# Bridge.net
KiCad netlist of a schematic drawn in Altium Designer
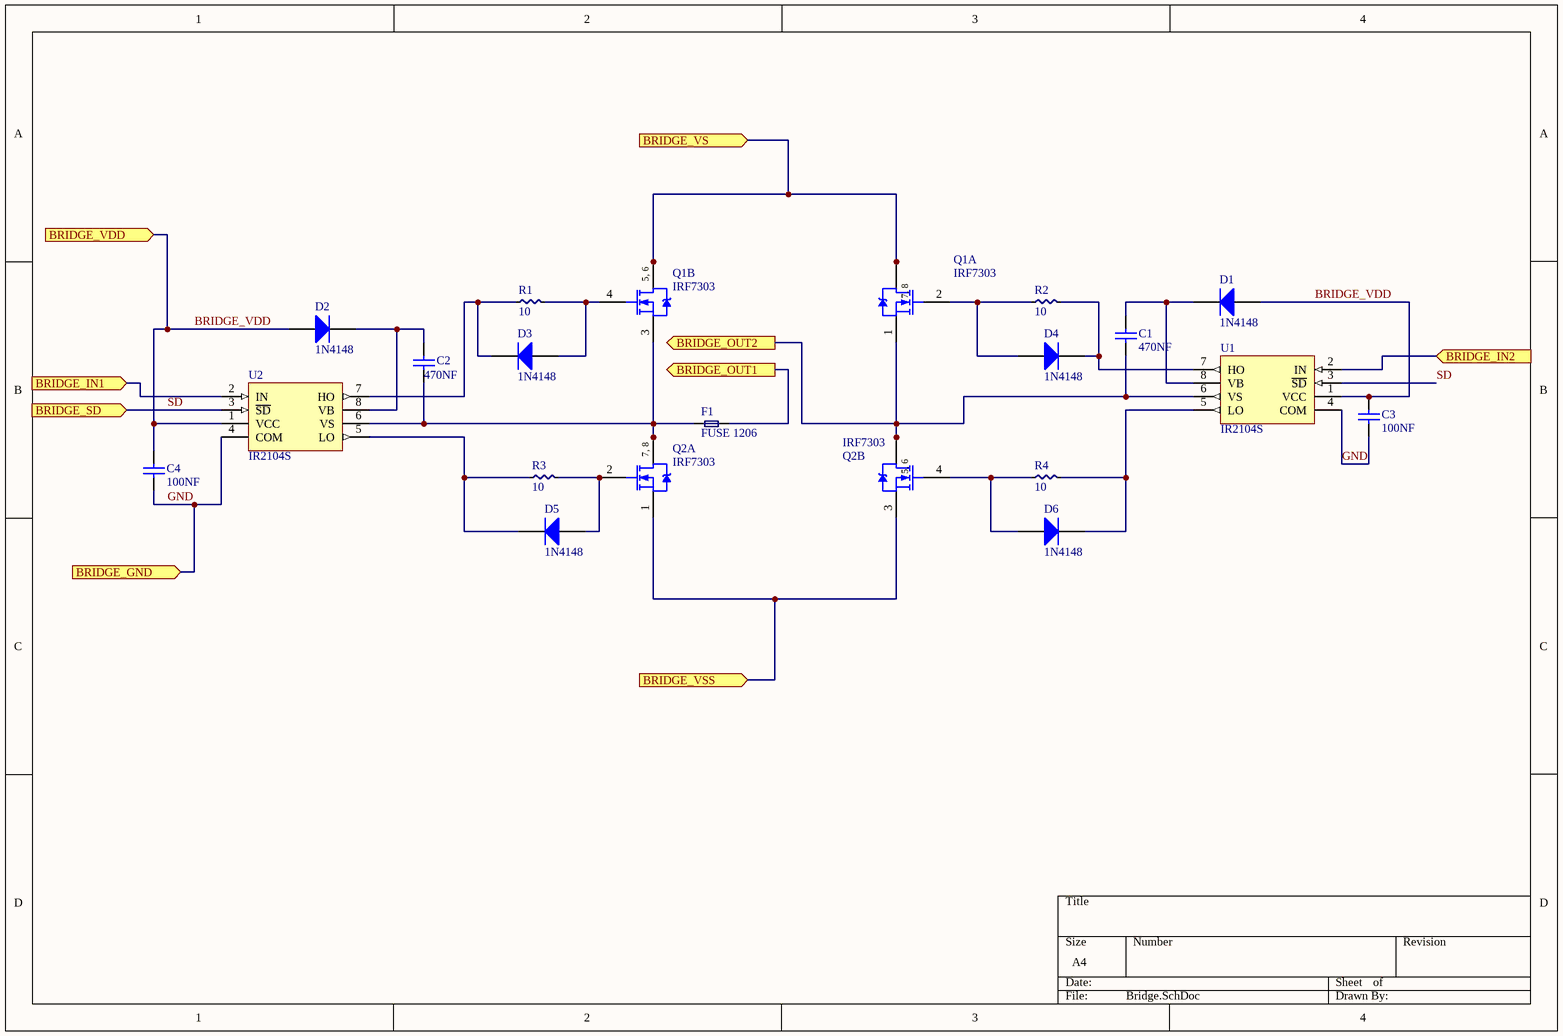
[diagram p0: Bridge.SchDoc]

(export (version "E")
  (design (tool "Eeschema 10.0.6"))
  (components
    (comp (ref "C1")
      (value "470NF")
      (footprint "MY_CAP_SMD_1206")
      (description "3.2 mm × 1.6 mm")
      (libsource (lib "AMINLIB") (part "CAP SMD_1206"))
    )
    (comp (ref "C2")
      (value "470NF")
      (footprint "MY_CAP_SMD_1206")
      (description "3.2 mm × 1.6 mm")
      (libsource (lib "AMINLIB") (part "CAP SMD_1206"))
    )
    (comp (ref "C3")
      (value "100NF")
      (footprint "MY_CAP_SMD_0805")
      (description "2.0 mm × 1.25 mm")
      (libsource (lib "AMINLIB") (part "CAP SMD_0805"))
    )
    (comp (ref "C4")
      (value "100NF")
      (footprint "MY_CAP_SMD_0805")
      (description "2.0 mm × 1.25 mm")
      (libsource (lib "AMINLIB") (part "CAP SMD_0805"))
    )
    (comp (ref "D1")
      (value "1N4148")
      (footprint "MY_DIOD1N5822_SMD")
      (libsource (lib "AMINLIB") (part "1N5822-smd-5*2mm"))
    )
    (comp (ref "D2")
      (value "1N4148")
      (footprint "MY_DIOD1N5822_SMD")
      (libsource (lib "AMINLIB") (part "1N5822-smd-5*2mm"))
    )
    (comp (ref "D3")
      (value "1N4148")
      (footprint "MY_DIOD1N5822_SMD")
      (libsource (lib "AMINLIB") (part "1N5822-smd-5*2mm"))
    )
    (comp (ref "D4")
      (value "1N4148")
      (footprint "MY_DIOD1N5822_SMD")
      (libsource (lib "AMINLIB") (part "1N5822-smd-5*2mm"))
    )
    (comp (ref "D5")
      (value "1N4148")
      (footprint "MY_DIOD1N5822_SMD")
      (libsource (lib "AMINLIB") (part "1N5822-smd-5*2mm"))
    )
    (comp (ref "D6")
      (value "1N4148")
      (footprint "MY_DIOD1N5822_SMD")
      (libsource (lib "AMINLIB") (part "1N5822-smd-5*2mm"))
    )
    (comp (ref "F1")
      (value "FUSE 1206")
      (footprint "FUSE1206")
      (libsource (lib "AMINLIB") (part "FUSE 1206"))
    )
    (comp (ref "Q1")
      (value "IRF7303")
      (footprint "SO-8_N")
      (description "HEXFET Power MOSFET")
      (fields (field (name "PUBLISHER") "Altium Limited"))
      (libsource (lib "IR Discrete MOSFET - Power") (part "IRF7303"))
    )
    (comp (ref "Q2")
      (value "IRF7303")
      (footprint "SO-8_N")
      (description "HEXFET Power MOSFET")
      (fields (field (name "PUBLISHER") "Altium Limited"))
      (libsource (lib "IR Discrete MOSFET - Power") (part "IRF7303"))
    )
    (comp (ref "R1")
      (value "10")
      (footprint "MY_RES_SMD_0805")
      (libsource (lib "AMINLIB") (part "RES SMD 0805"))
    )
    (comp (ref "R2")
      (value "10")
      (footprint "MY_RES_SMD_0805")
      (libsource (lib "AMINLIB") (part "RES SMD 0805"))
    )
    (comp (ref "R3")
      (value "10")
      (footprint "MY_RES_SMD_0805")
      (libsource (lib "AMINLIB") (part "RES SMD 0805"))
    )
    (comp (ref "R4")
      (value "10")
      (footprint "MY_RES_SMD_0805")
      (libsource (lib "AMINLIB") (part "RES SMD 0805"))
    )
    (comp (ref "U1")
      (value "IR2104S")
      (footprint "SO-8_N")
      (description "High and Low Side Driver")
      (fields (field (name "PUBLISHER") "Altium Limited"))
      (libsource (lib "") (part "IR2104S_1"))
    )
    (comp (ref "U2")
      (value "IR2104S")
      (footprint "SO-8_N")
      (description "High and Low Side Driver")
      (fields (field (name "PUBLISHER") "Altium Limited"))
      (libsource (lib "IR Interface Bridge Driver") (part "IR2104S"))
    )
  )
  (nets
    (net (code "1") (name "/BRIDGE_IN1") (class "Default")
      (node (ref "U2") (pin "2") (pinfunction "IN_2") (pintype "input"))
    )
    (net (code "2") (name "/BRIDGE_IN2") (class "Default")
      (node (ref "U1") (pin "2") (pinfunction "IN_2") (pintype "input"))
    )
    (net (code "3") (name "/BRIDGE_OUT1") (class "Default")
      (node (ref "F1") (pin "1") (pinfunction "1_1") (pintype "passive"))
    )
    (net (code "4") (name "/BRIDGE_OUT2") (class "Default")
      (node (ref "C1") (pin "1") (pinfunction "1_1") (pintype "passive"))
      (node (ref "Q1") (pin "1") (pinfunction "S_1") (pintype "passive"))
      (node (ref "Q2") (pin "5") (pinfunction "D_5") (pintype "passive"))
      (node (ref "Q2") (pin "6") (pinfunction "D_6") (pintype "passive"))
      (node (ref "U1") (pin "6") (pinfunction "VS_6") (pintype "output"))
    )
    (net (code "5") (name "/BRIDGE_VDD") (class "Default")
      (node (ref "C3") (pin "2") (pinfunction "2_2") (pintype "passive"))
      (node (ref "C4") (pin "2") (pinfunction "2_2") (pintype "passive"))
      (node (ref "D1") (pin "A") (pinfunction "A_A") (pintype "passive"))
      (node (ref "D2") (pin "A") (pinfunction "A_A") (pintype "passive"))
      (node (ref "U1") (pin "1") (pinfunction "VCC_1") (pintype "passive"))
      (node (ref "U2") (pin "1") (pinfunction "VCC_1") (pintype "passive"))
    )
    (net (code "6") (name "/BRIDGE_VS") (class "Default")
      (node (ref "Q1") (pin "5") (pinfunction "D_5") (pintype "passive"))
      (node (ref "Q1") (pin "6") (pinfunction "D_6") (pintype "passive"))
      (node (ref "Q1") (pin "7") (pinfunction "D_7") (pintype "passive"))
      (node (ref "Q1") (pin "8") (pinfunction "D_8") (pintype "passive"))
    )
    (net (code "7") (name "/BRIDGE_VSS") (class "Default")
      (node (ref "Q2") (pin "1") (pinfunction "S_1") (pintype "passive"))
      (node (ref "Q2") (pin "3") (pinfunction "S_3") (pintype "passive"))
    )
    (net (code "8") (name "/GND") (class "Default")
      (node (ref "C3") (pin "1") (pinfunction "1_1") (pintype "passive"))
      (node (ref "C4") (pin "1") (pinfunction "1_1") (pintype "passive"))
      (node (ref "U1") (pin "4") (pinfunction "COM_4") (pintype "passive"))
      (node (ref "U2") (pin "4") (pinfunction "COM_4") (pintype "passive"))
    )
    (net (code "9") (name "/SD") (class "Default")
      (node (ref "U1") (pin "3") (pinfunction "~{SD}_3") (pintype "input"))
      (node (ref "U2") (pin "3") (pinfunction "~{SD}_3") (pintype "input"))
    )
    (net (code "10") (name "Net-(Q1A-G)") (class "Default")
      (node (ref "D4") (pin "A") (pinfunction "A_A") (pintype "passive"))
      (node (ref "Q1") (pin "2") (pinfunction "G_2") (pintype "passive"))
      (node (ref "R2") (pin "1") (pinfunction "1_1") (pintype "passive"))
    )
    (net (code "11") (name "Net-(Q1B-G)") (class "Default")
      (node (ref "D3") (pin "A") (pinfunction "A_A") (pintype "passive"))
      (node (ref "Q1") (pin "4") (pinfunction "G_4") (pintype "passive"))
      (node (ref "R1") (pin "2") (pinfunction "2_2") (pintype "passive"))
    )
    (net (code "12") (name "Net-(Q1B-S)") (class "Default")
      (node (ref "C2") (pin "1") (pinfunction "1_1") (pintype "passive"))
      (node (ref "F1") (pin "2") (pinfunction "2_2") (pintype "passive"))
      (node (ref "Q1") (pin "3") (pinfunction "S_3") (pintype "passive"))
      (node (ref "Q2") (pin "7") (pinfunction "D_7") (pintype "passive"))
      (node (ref "Q2") (pin "8") (pinfunction "D_8") (pintype "passive"))
      (node (ref "U2") (pin "6") (pinfunction "VS_6") (pintype "power_in"))
    )
    (net (code "13") (name "Net-(Q2A-G)") (class "Default")
      (node (ref "D5") (pin "A") (pinfunction "A_A") (pintype "passive"))
      (node (ref "Q2") (pin "2") (pinfunction "G_2") (pintype "passive"))
      (node (ref "R3") (pin "2") (pinfunction "2_2") (pintype "passive"))
    )
    (net (code "14") (name "Net-(Q2B-G)") (class "Default")
      (node (ref "D6") (pin "A") (pinfunction "A_A") (pintype "passive"))
      (node (ref "Q2") (pin "4") (pinfunction "G_4") (pintype "passive"))
      (node (ref "R4") (pin "1") (pinfunction "1_1") (pintype "passive"))
    )
    (net (code "15") (name "Net-(U1-HO)") (class "Default")
      (node (ref "D4") (pin "K") (pinfunction "K_K") (pintype "passive"))
      (node (ref "R2") (pin "2") (pinfunction "2_2") (pintype "passive"))
      (node (ref "U1") (pin "7") (pinfunction "HO_7") (pintype "output"))
    )
    (net (code "16") (name "Net-(U1-LO)") (class "Default")
      (node (ref "D6") (pin "K") (pinfunction "K_K") (pintype "passive"))
      (node (ref "R4") (pin "2") (pinfunction "2_2") (pintype "passive"))
      (node (ref "U1") (pin "5") (pinfunction "LO_5") (pintype "output"))
    )
    (net (code "17") (name "Net-(U1-VB)") (class "Default")
      (node (ref "C1") (pin "2") (pinfunction "2_2") (pintype "passive"))
      (node (ref "D1") (pin "K") (pinfunction "K_K") (pintype "passive"))
      (node (ref "U1") (pin "8") (pinfunction "VB_8") (pintype "power_in"))
    )
    (net (code "18") (name "Net-(U2-HO)") (class "Default")
      (node (ref "D3") (pin "K") (pinfunction "K_K") (pintype "passive"))
      (node (ref "R1") (pin "1") (pinfunction "1_1") (pintype "passive"))
      (node (ref "U2") (pin "7") (pinfunction "HO_7") (pintype "output"))
    )
    (net (code "19") (name "Net-(U2-LO)") (class "Default")
      (node (ref "D5") (pin "K") (pinfunction "K_K") (pintype "passive"))
      (node (ref "R3") (pin "1") (pinfunction "1_1") (pintype "passive"))
      (node (ref "U2") (pin "5") (pinfunction "LO_5") (pintype "output"))
    )
    (net (code "20") (name "Net-(U2-VB)") (class "Default")
      (node (ref "C2") (pin "2") (pinfunction "2_2") (pintype "passive"))
      (node (ref "D2") (pin "K") (pinfunction "K_K") (pintype "passive"))
      (node (ref "U2") (pin "8") (pinfunction "VB_8") (pintype "power_in"))
    )
  )
)
